# artik530_carrierboard.net
KiCad netlist of a schematic drawn in EAGLE
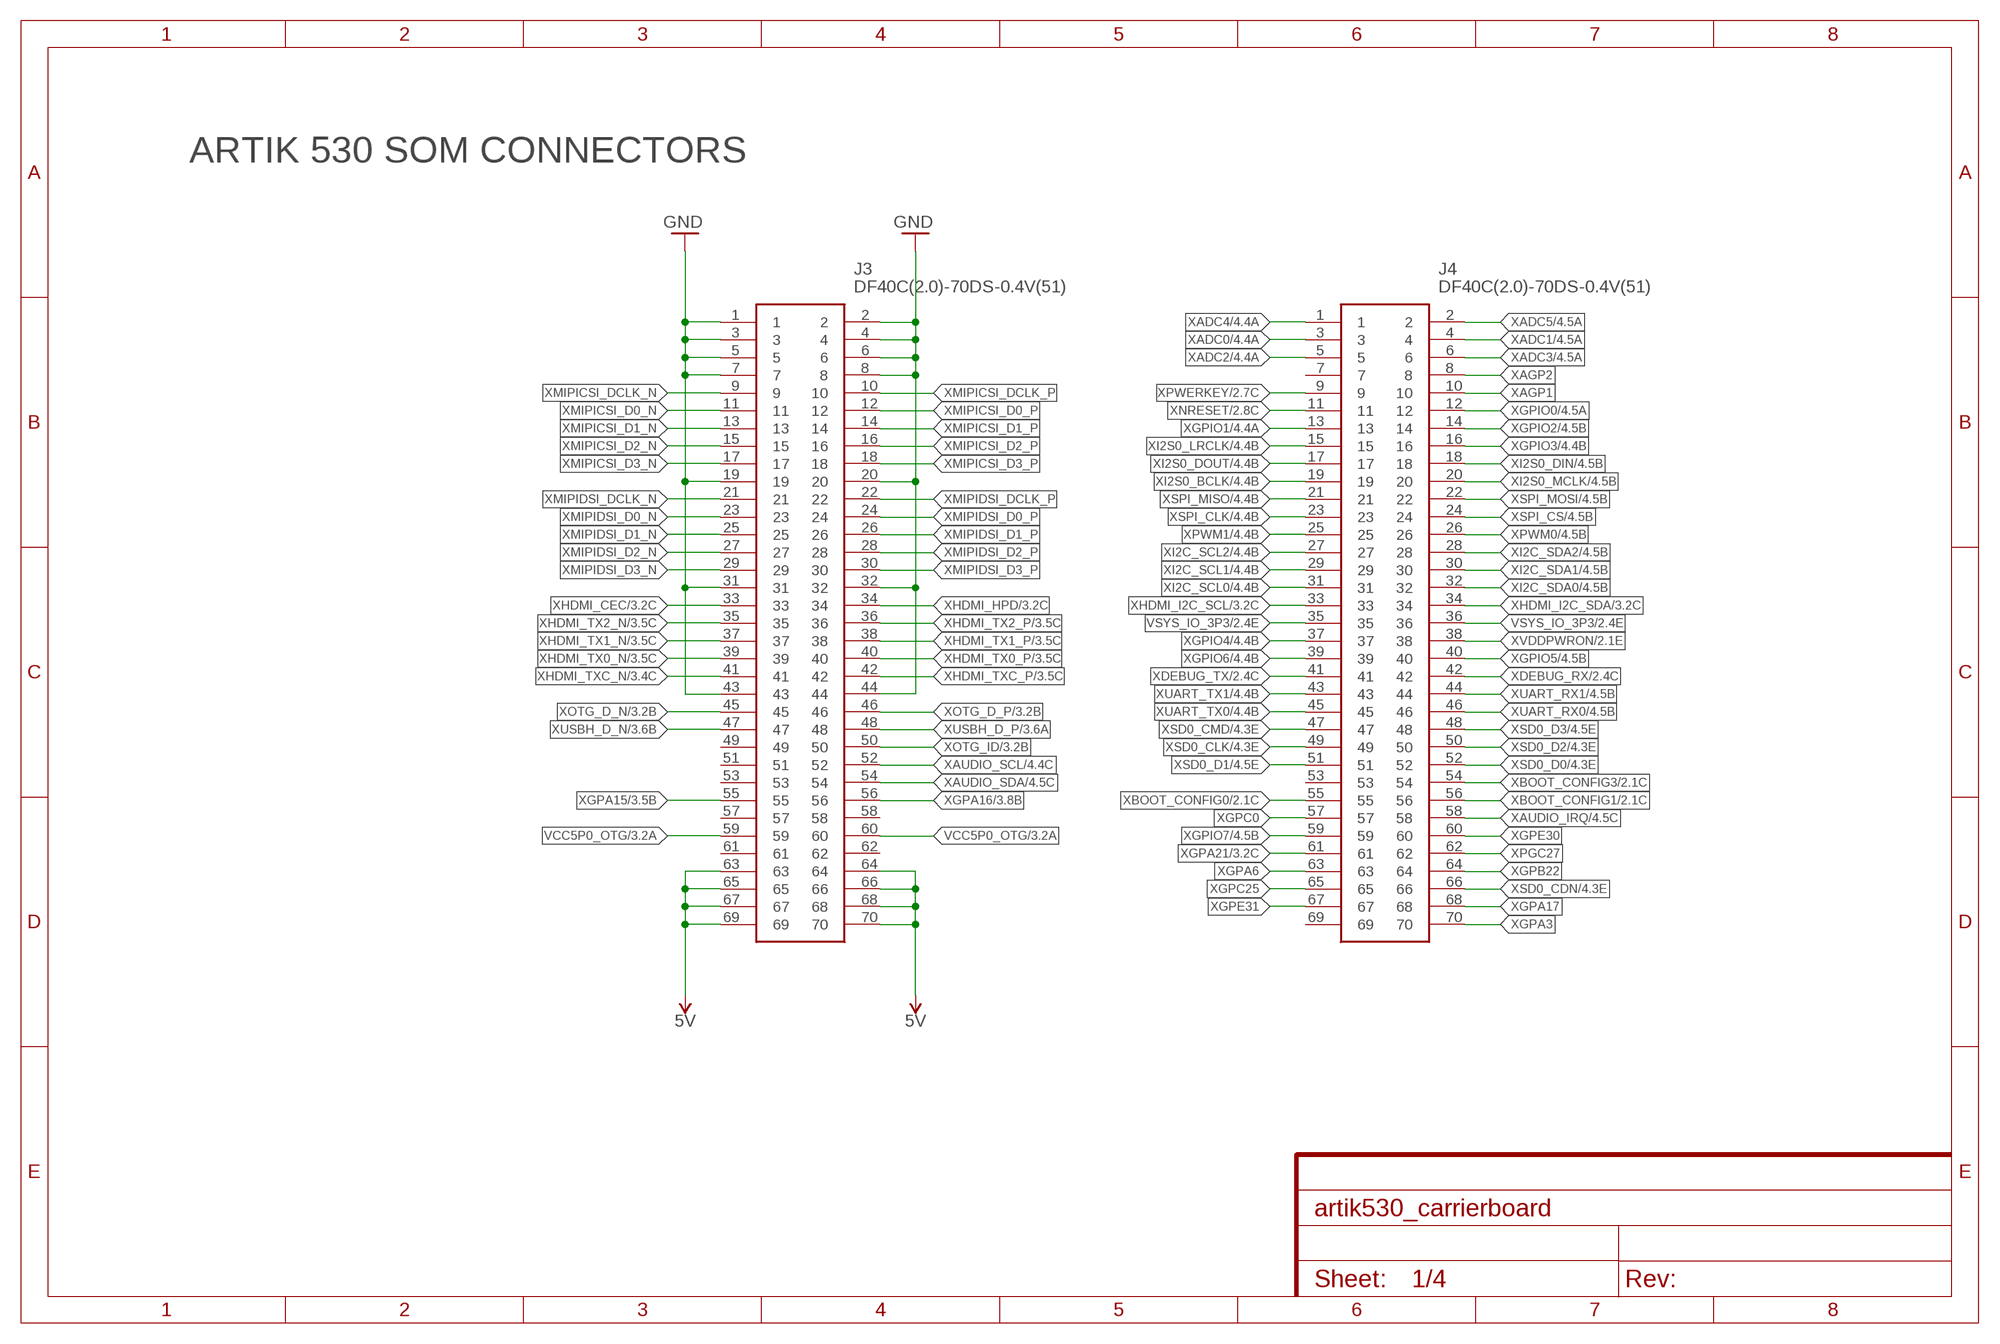
[diagram p0: schematic, sheet 1]
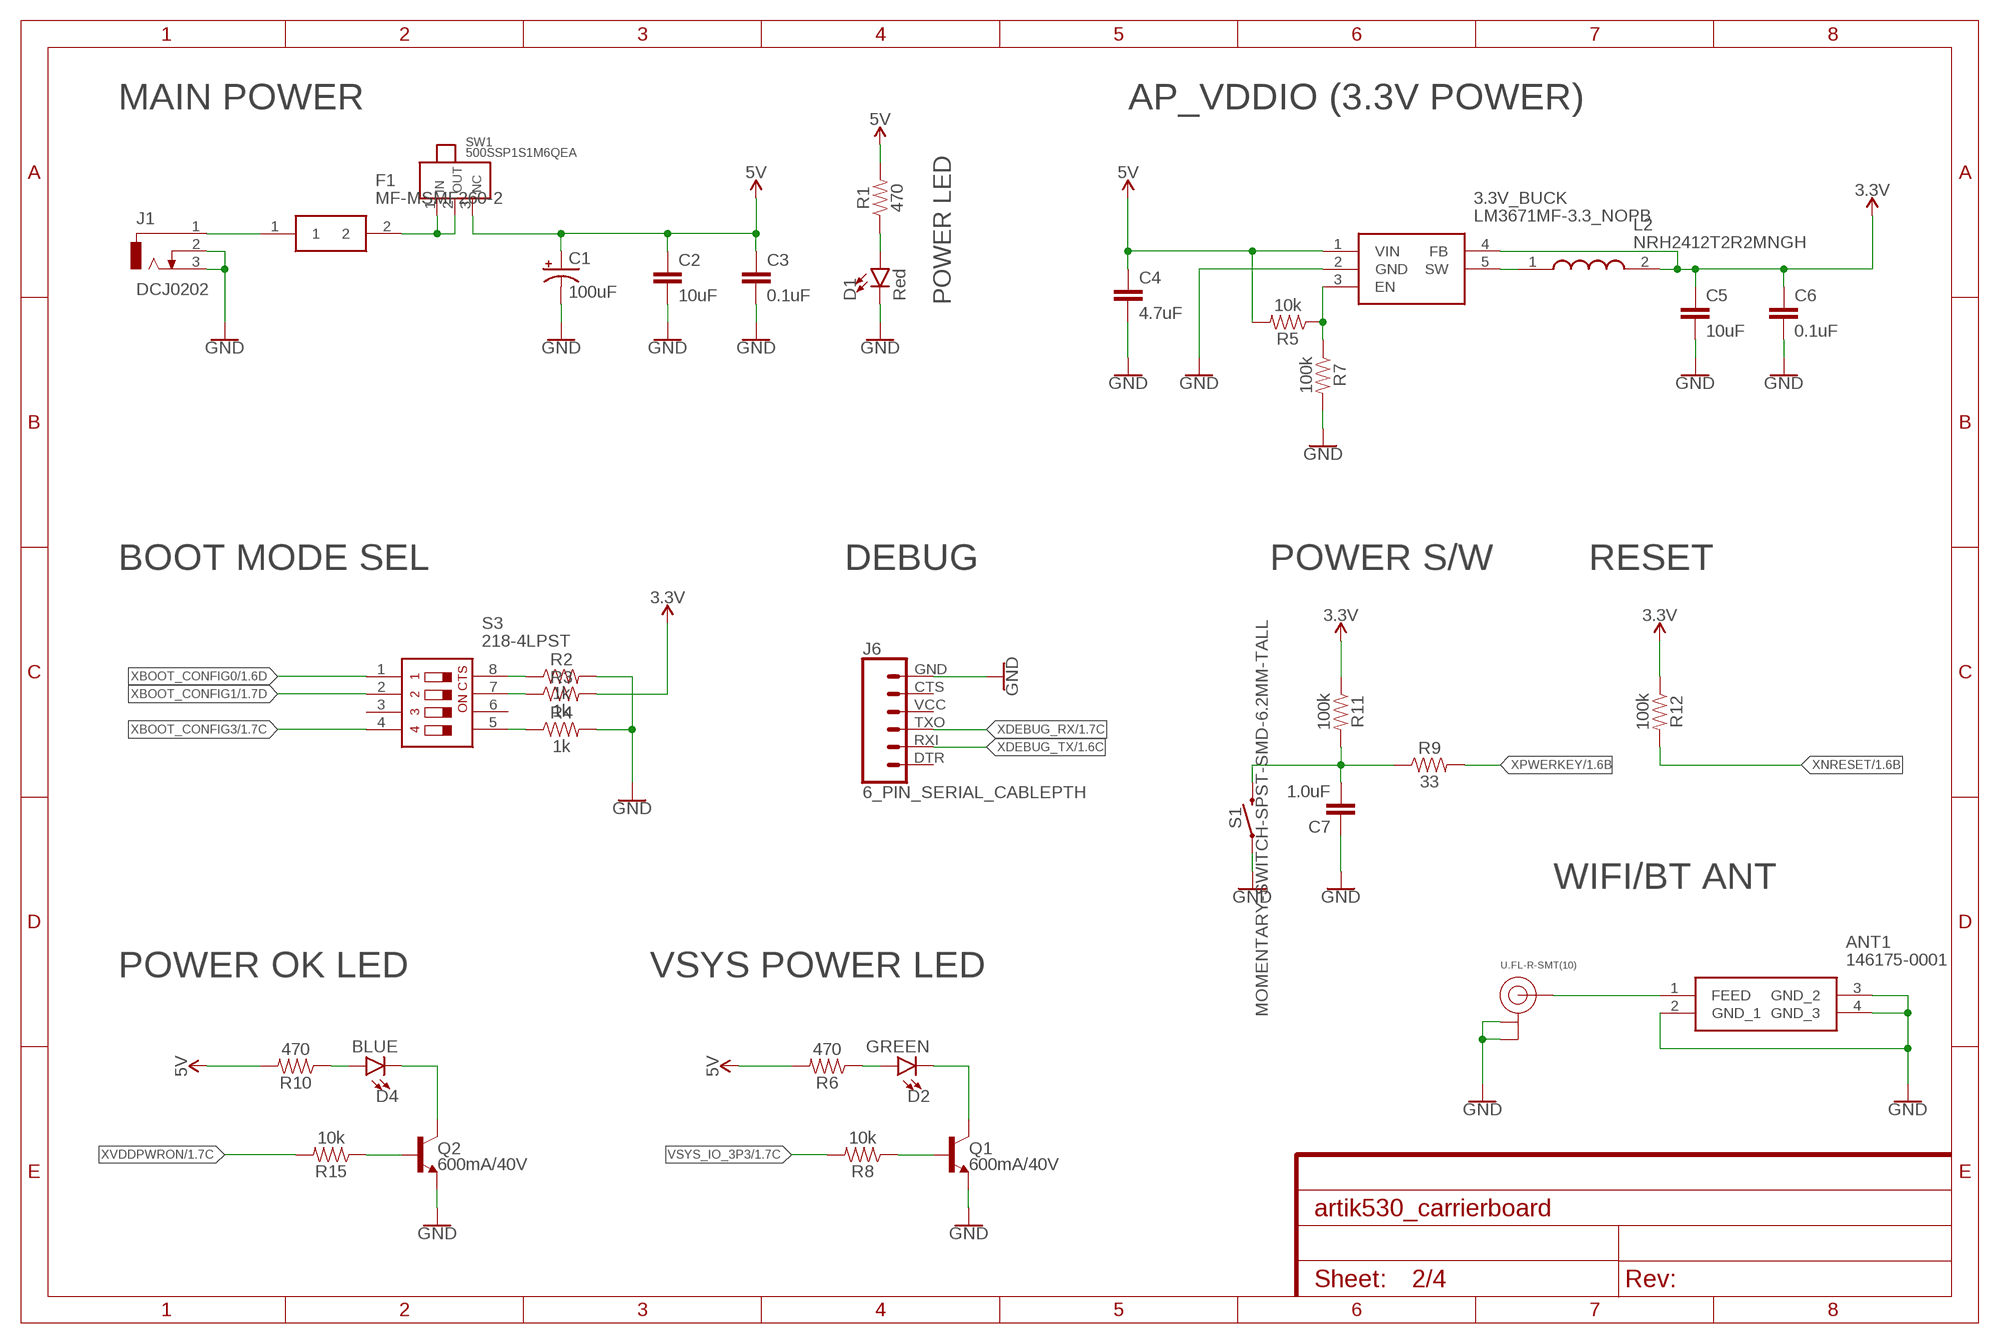
[diagram p1: schematic, sheet 2]
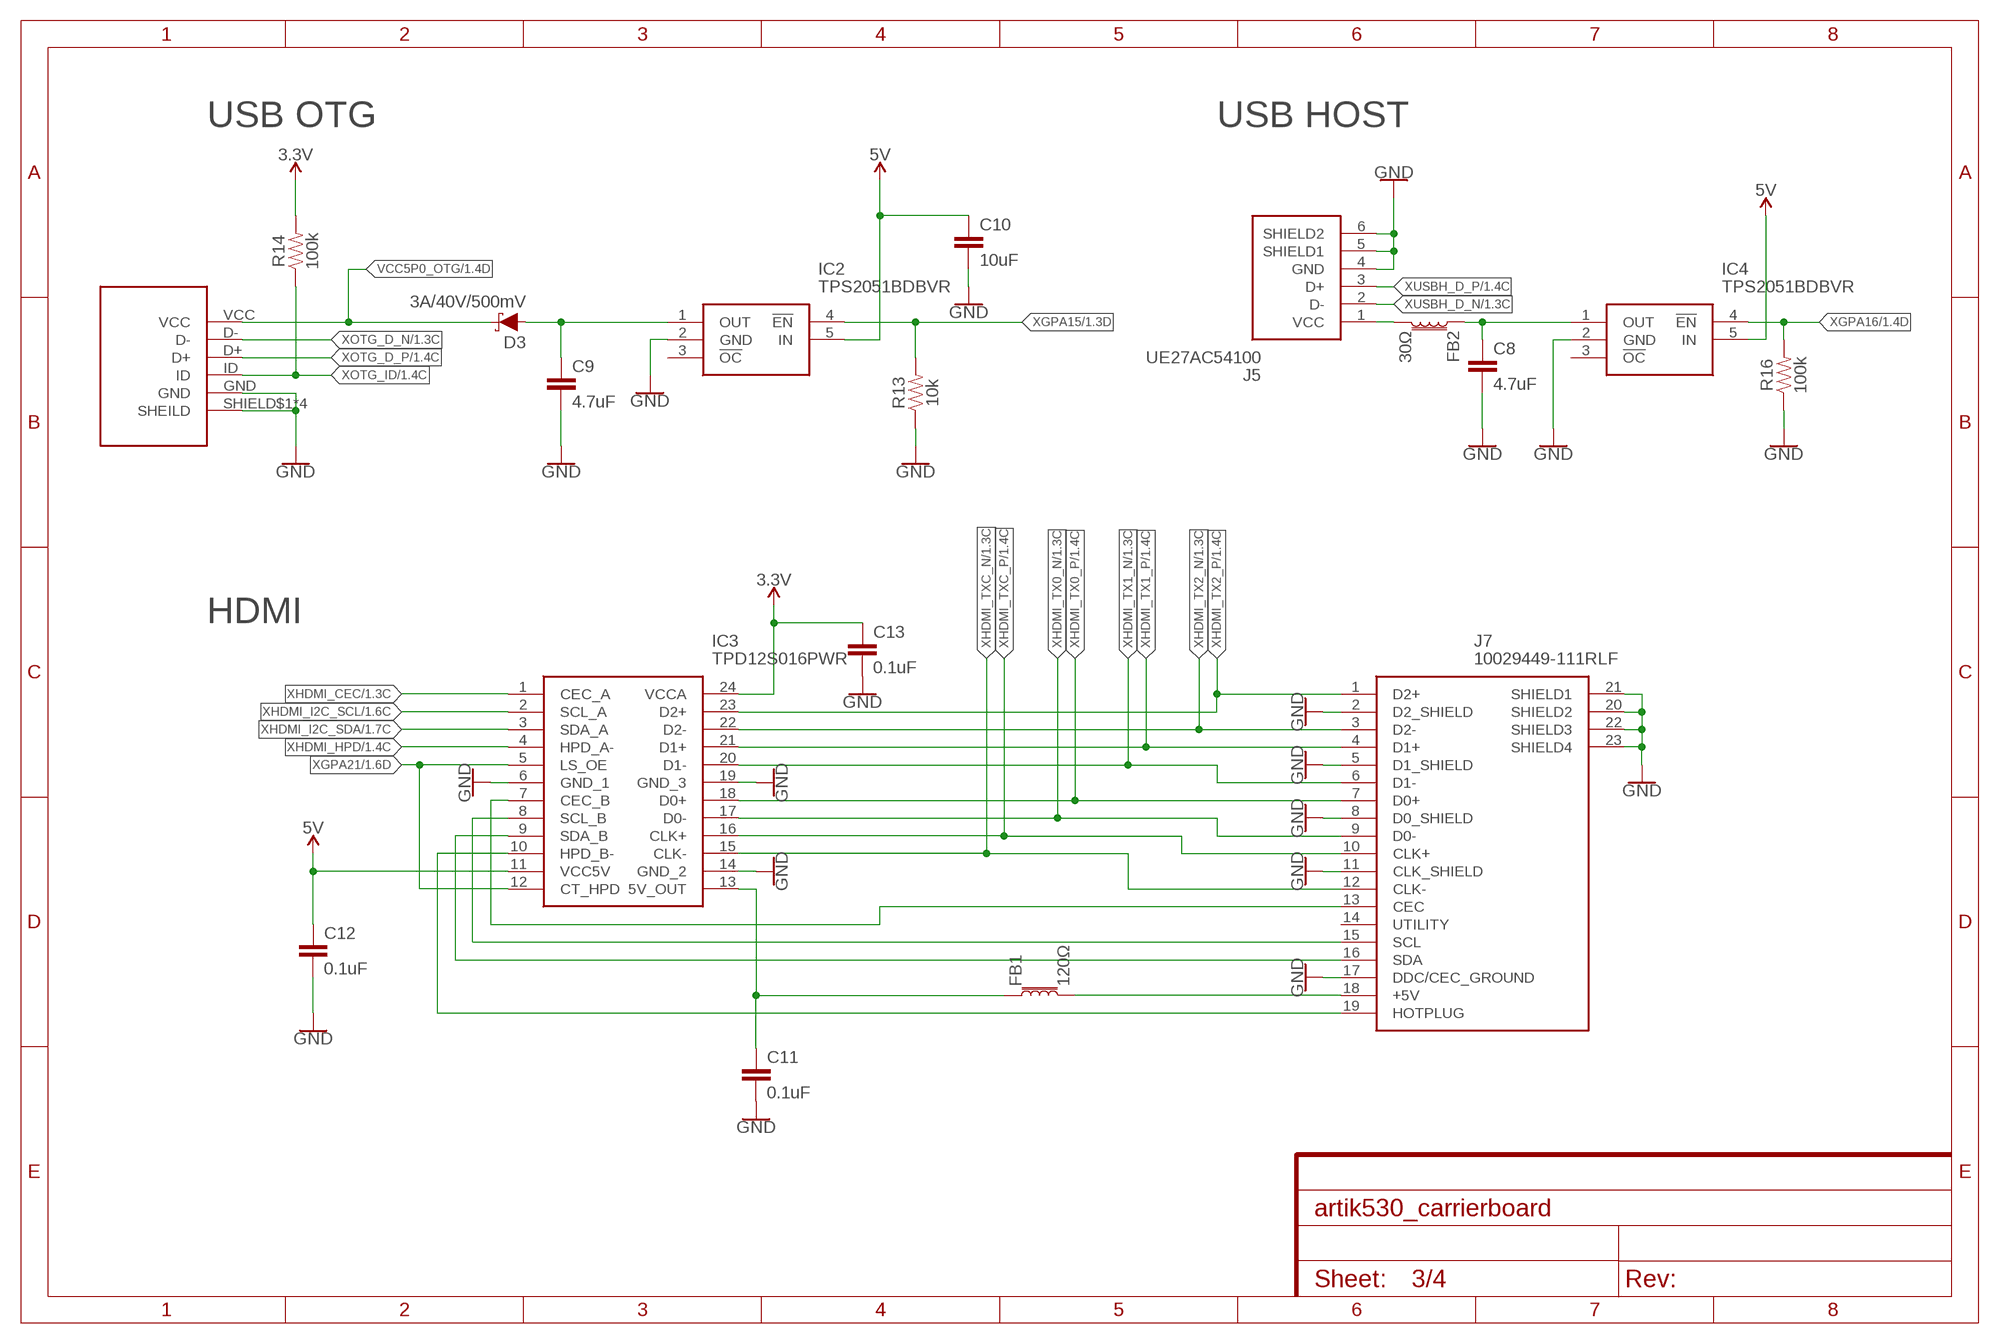
[diagram p2: schematic, sheet 3]
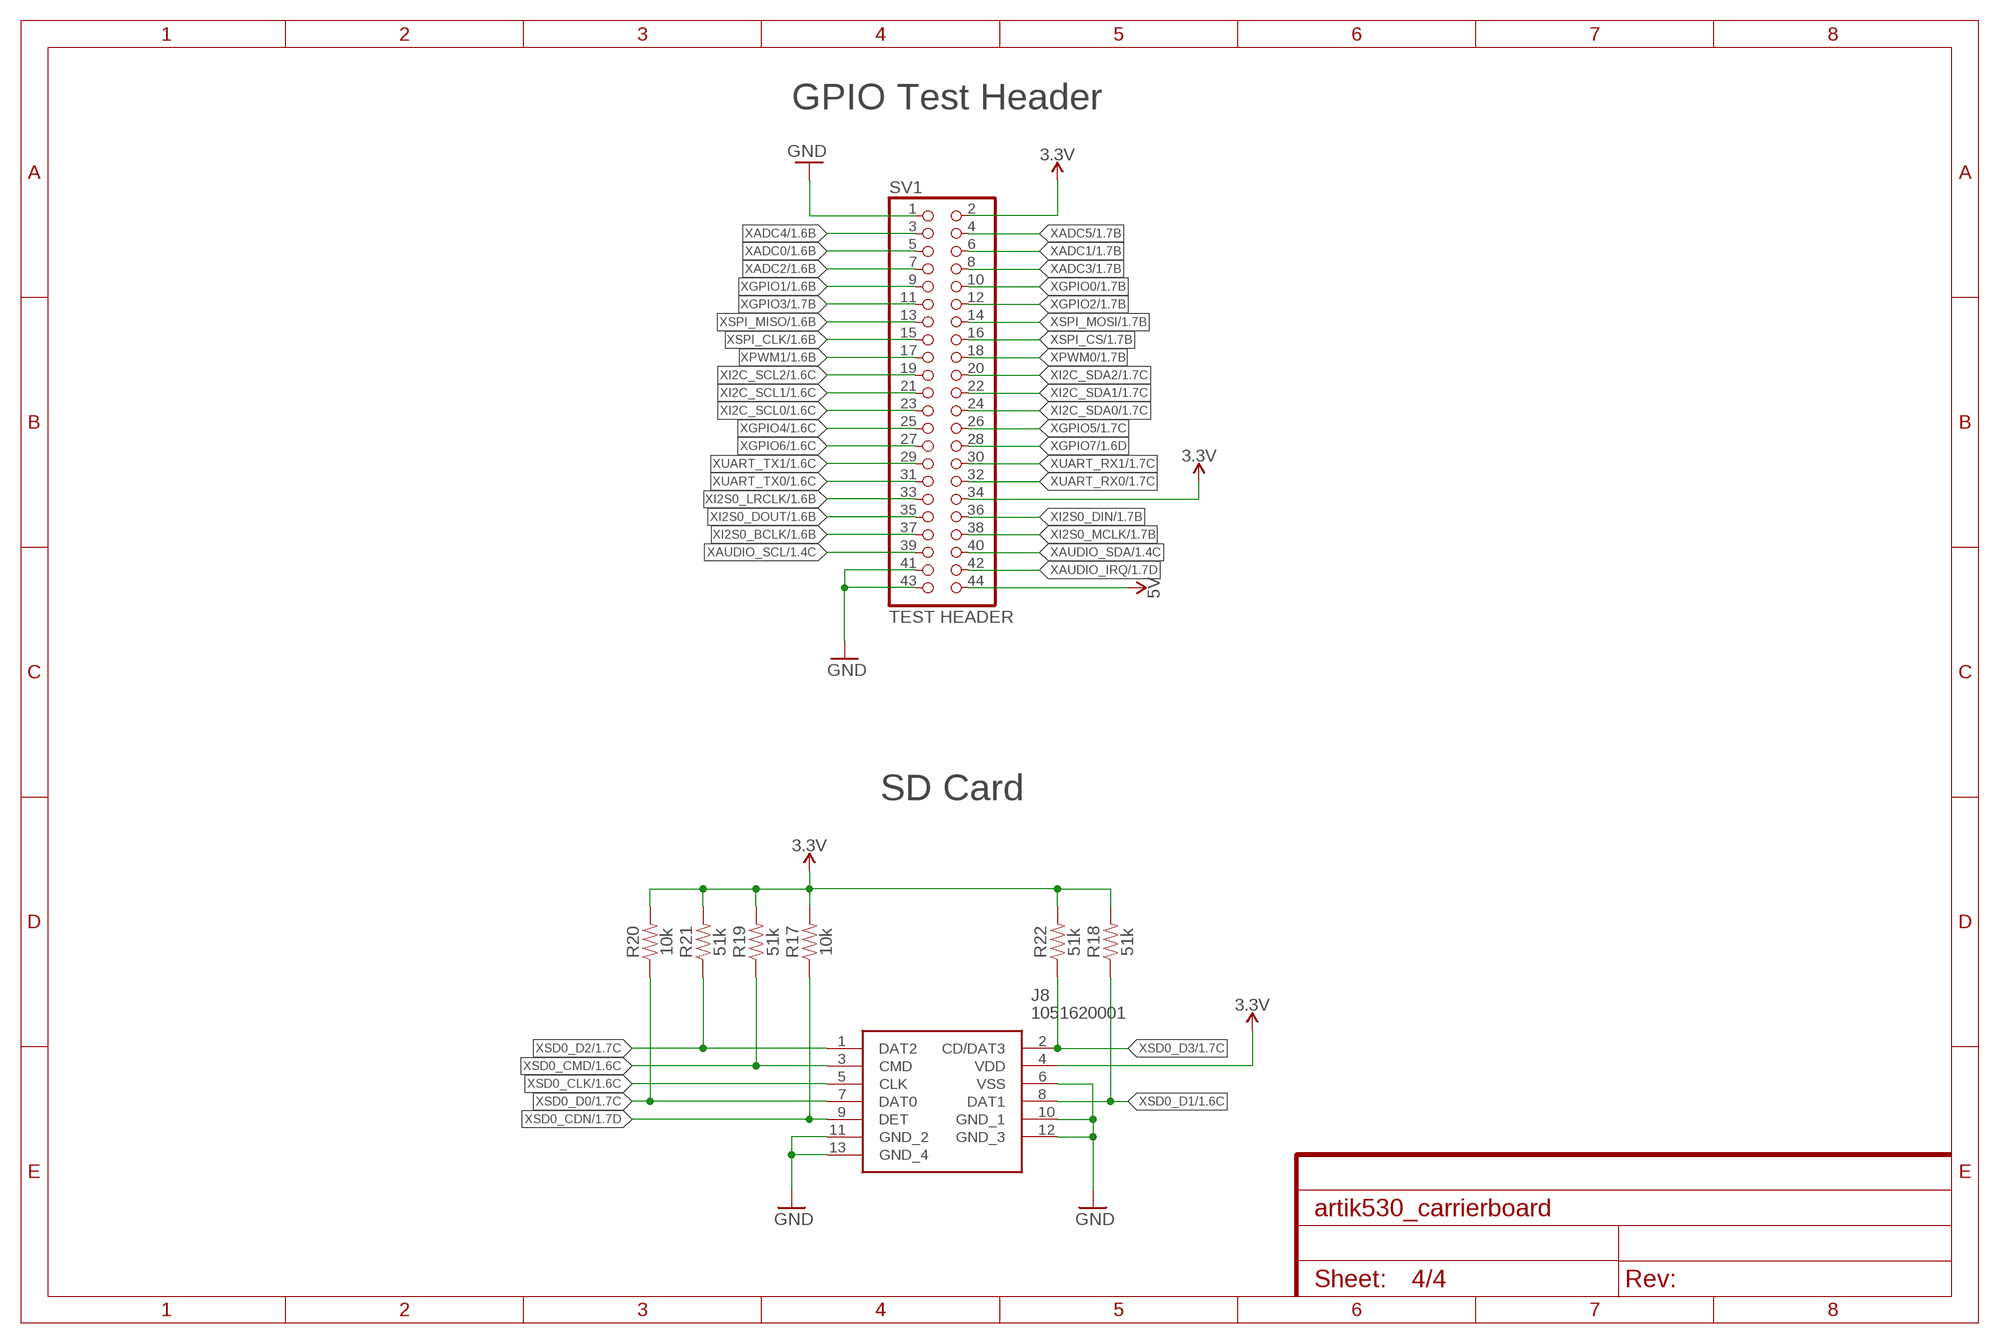
[diagram p3: schematic, sheet 4]

(export (version "E")
  (design (tool "Eeschema 10.0.6"))
  (components
    (comp (ref "C8")
      (value "4.7uF")
      (footprint "eagle-import:0603")
      (libsource (lib "eagle-import") (part "4.7UF-0603-6.3V-(10%)"))
    )
    (comp (ref "C9")
      (value "4.7uF")
      (footprint "eagle-import:0603")
      (libsource (lib "eagle-import") (part "4.7UF-0603-6.3V-(10%)"))
    )
    (comp (ref "C10")
      (value "10uF")
      (footprint "eagle-import:0603")
      (libsource (lib "eagle-import") (part "10UF-0603-6.3V-20%"))
    )
    (comp (ref "C11")
      (value "0.1uF")
      (footprint "eagle-import:0603")
      (libsource (lib "eagle-import") (part "0.1UF-0603-25V-(+80/-20%)"))
    )
    (comp (ref "C12")
      (value "0.1uF")
      (footprint "eagle-import:0603")
      (libsource (lib "eagle-import") (part "0.1UF-0603-25V-(+80/-20%)"))
    )
    (comp (ref "C13")
      (value "0.1uF")
      (footprint "eagle-import:0603")
      (libsource (lib "eagle-import") (part "0.1UF-0603-25V-(+80/-20%)"))
    )
    (comp (ref "D3")
      (value "3A/40V/500mV")
      (footprint "eagle-import:SMA-DIODE")
      (libsource (lib "eagle-import") (part "DIODE-SCHOTTKY-B340A"))
    )
    (comp (ref "FB1")
      (value "120Ω")
      (footprint "eagle-import:0603")
      (libsource (lib "eagle-import") (part "FERRITE_BEAD-0603"))
    )
    (comp (ref "FB2")
      (value "30Ω")
      (footprint "eagle-import:0603")
      (libsource (lib "eagle-import") (part "FERRITE_BEAD-0603"))
    )
    (comp (ref "IC2")
      (value "TPS2051BDBVR")
      (footprint "eagle-import:SOT95P280X145-5N")
      (libsource (lib "eagle-import") (part "TPS2051BDBVR"))
    )
    (comp (ref "IC3")
      (value "TPD12S016PWR")
      (footprint "eagle-import:SOP65P640X120-24N")
      (fields (field (name "RS_PART_NUMBER") "1627865"))
      (libsource (lib "eagle-import") (part "TPD12S016PWR"))
    )
    (comp (ref "IC4")
      (value "TPS2051BDBVR")
      (footprint "eagle-import:SOT95P280X145-5N")
      (libsource (lib "eagle-import") (part "TPS2051BDBVR"))
    )
    (comp (ref "J2")
      (value "10118193-0001LF")
      (footprint "eagle-import:10118193-0001LF")
      (libsource (lib "eagle-import") (part "10118193-0001LF"))
    )
    (comp (ref "J5")
      (value "UE27AC54100")
      (footprint "eagle-import:UE27AC54100")
      (libsource (lib "eagle-import") (part "UE27AC54100"))
    )
    (comp (ref "J7")
      (value "10029449-111RLF")
      (footprint "eagle-import:10029449-111RLF_1")
      (libsource (lib "eagle-import") (part "10029449-111RLF"))
    )
    (comp (ref "R13")
      (value "10k")
      (footprint "eagle-import:0603")
      (libsource (lib "eagle-import") (part "10KOHM-0603-1/10W-1%"))
    )
    (comp (ref "R14")
      (value "100k")
      (footprint "eagle-import:0603")
      (libsource (lib "eagle-import") (part "100KOHM-0603-1/10W-1%"))
    )
    (comp (ref "R16")
      (value "100k")
      (footprint "eagle-import:0603")
      (libsource (lib "eagle-import") (part "100KOHM-0603-1/10W-1%"))
    )
    (comp (ref "3.3V_BUCK")
      (value "LM3671MF-3.3_NOPB")
      (footprint "eagle-import:SOT95P284X122-5N")
      (fields
        (field (name "DIGIKEY_PART_NUMBER") "LM3671MF-3.3/NOPBTR-ND")
        (field (name "MANUFACTURER_PART_NUMBER") "LM3671MF-3.3/NOPB")
      )
      (libsource (lib "eagle-import") (part "LM3671MF-3.3_NOPB"))
    )
    (comp (ref "ANT1")
      (value "146175-0001")
      (footprint "eagle-import:146175-0001")
      (libsource (lib "eagle-import") (part "146175-0001"))
    )
    (comp (ref "C1")
      (value "100uF")
      (footprint "eagle-import:EIA7343")
      (libsource (lib "eagle-import") (part "100UF-POLAR-EIA7343-10V-10%(TANT)"))
    )
    (comp (ref "C2")
      (value "10uF")
      (footprint "eagle-import:0603")
      (libsource (lib "eagle-import") (part "10UF-0603-6.3V-20%"))
    )
    (comp (ref "C3")
      (value "0.1uF")
      (footprint "eagle-import:0603")
      (libsource (lib "eagle-import") (part "0.1UF-0603-25V-(+80/-20%)"))
    )
    (comp (ref "C4")
      (value "4.7uF")
      (footprint "eagle-import:0603")
      (libsource (lib "eagle-import") (part "4.7UF-0603-6.3V-(10%)"))
    )
    (comp (ref "C5")
      (value "10uF")
      (footprint "eagle-import:0603")
      (libsource (lib "eagle-import") (part "10UF-0603-6.3V-20%"))
    )
    (comp (ref "C6")
      (value "0.1uF")
      (footprint "eagle-import:0603")
      (libsource (lib "eagle-import") (part "0.1UF-0603-25V-(+80/-20%)"))
    )
    (comp (ref "C7")
      (value "1.0uF")
      (footprint "eagle-import:0603")
      (libsource (lib "eagle-import") (part "1.0UF-0603-16V-10%"))
    )
    (comp (ref "D1")
      (value "Red")
      (footprint "eagle-import:LED-0603")
      (libsource (lib "eagle-import") (part "LED-RED0603-SMART"))
    )
    (comp (ref "D2")
      (value "GREEN")
      (footprint "eagle-import:LED-0603")
      (libsource (lib "eagle-import") (part "LED-GREEN0603"))
    )
    (comp (ref "D4")
      (value "BLUE")
      (footprint "eagle-import:LED-0603")
      (libsource (lib "eagle-import") (part "LED-GREEN0603"))
    )
    (comp (ref "F1")
      (value "MF-MSMF260-2")
      (footprint "eagle-import:MF-MSMF260-2")
      (fields (field (name "RS_PART_NUMBER") "6478257P"))
      (libsource (lib "eagle-import") (part "MF-MSMF260-2"))
    )
    (comp (ref "J1")
      (value "DCJ0202")
      (footprint "eagle-import:DCJ0202")
      (libsource (lib "eagle-import") (part "DCJ0202"))
    )
    (comp (ref "J6")
      (value "6_PIN_SERIAL_CABLEPTH")
      (footprint "eagle-import:FTDI_BASIC")
      (libsource (lib "eagle-import") (part "6_PIN_SERIAL_CABLEPTH"))
    )
    (comp (ref "L2")
      (value "NRH2412T2R2MNGH")
      (footprint "eagle-import:NRH2412T2R2MNGH")
      (libsource (lib "eagle-import") (part "NRH2412T2R2MNGH"))
    )
    (comp (ref "Q1")
      (value "600mA/40V")
      (footprint "eagle-import:SOT23-3")
      (libsource (lib "eagle-import") (part "TRANS_NPN-MMBT2222AL"))
    )
    (comp (ref "Q2")
      (value "600mA/40V")
      (footprint "eagle-import:SOT23-3")
      (libsource (lib "eagle-import") (part "TRANS_NPN-MMBT2222AL"))
    )
    (comp (ref "R1")
      (value "470")
      (footprint "eagle-import:0603")
      (libsource (lib "eagle-import") (part "470OHM-0603-1/10W-1%"))
    )
    (comp (ref "R2")
      (value "1k")
      (footprint "eagle-import:0603")
      (libsource (lib "eagle-import") (part "1KOHM-0603-1/10W-1%"))
    )
    (comp (ref "R3")
      (value "1k")
      (footprint "eagle-import:0603")
      (libsource (lib "eagle-import") (part "1KOHM-0603-1/10W-1%"))
    )
    (comp (ref "R4")
      (value "1k")
      (footprint "eagle-import:0603")
      (libsource (lib "eagle-import") (part "1KOHM-0603-1/10W-1%"))
    )
    (comp (ref "R5")
      (value "10k")
      (footprint "eagle-import:0603")
      (libsource (lib "eagle-import") (part "10KOHM-0603-1/10W-1%"))
    )
    (comp (ref "R6")
      (value "470")
      (footprint "eagle-import:0603")
      (libsource (lib "eagle-import") (part "470OHM-0603-1/10W-1%"))
    )
    (comp (ref "R7")
      (value "100k")
      (footprint "eagle-import:0603")
      (libsource (lib "eagle-import") (part "100KOHM-0603-1/10W-1%"))
    )
    (comp (ref "R8")
      (value "10k")
      (footprint "eagle-import:0603")
      (libsource (lib "eagle-import") (part "10KOHM-0603-1/10W-1%"))
    )
    (comp (ref "R9")
      (value "33")
      (footprint "eagle-import:0603")
      (libsource (lib "eagle-import") (part "33OHM-0603-1/10W-1%"))
    )
    (comp (ref "R10")
      (value "470")
      (footprint "eagle-import:0603")
      (libsource (lib "eagle-import") (part "470OHM-0603-1/10W-1%"))
    )
    (comp (ref "R11")
      (value "100k")
      (footprint "eagle-import:0603")
      (libsource (lib "eagle-import") (part "100KOHM-0603-1/10W-1%"))
    )
    (comp (ref "R12")
      (value "100k")
      (footprint "eagle-import:0603")
      (libsource (lib "eagle-import") (part "100KOHM-0603-1/10W-1%"))
    )
    (comp (ref "R15")
      (value "10k")
      (footprint "eagle-import:0603")
      (libsource (lib "eagle-import") (part "10KOHM-0603-1/10W-1%"))
    )
    (comp (ref "S1")
      (value "MOMENTARY-SWITCH-SPST-SMD-6.2MM-TALL")
      (footprint "eagle-import:TACTILE_SWITCH_SMD_6.2MM_TALL")
      (libsource (lib "eagle-import") (part "MOMENTARY-SWITCH-SPST-SMD-6.2MM-TALL"))
    )
    (comp (ref "S3")
      (value "218-4LPST")
      (footprint "eagle-import:SOIC127P844X265-8N")
      (libsource (lib "eagle-import") (part "218-4LPST"))
    )
    (comp (ref "SW1")
      (value "500SSP1S1M6QEA")
      (footprint "eagle-import:500SSP1S1M6QEA")
      (libsource (lib "eagle-import") (part "500SSP1S1M6QEA"))
    )
    (comp (ref "U$3")
      (value "U.FL-R-SMT(10)")
      (footprint "eagle-import:U.FL-R-SMT(10)")
      (libsource (lib "eagle-import") (part "U.FL-R-SMT(10)"))
    )
    (comp (ref "J3")
      (value "DF40C(2.0)-70DS-0.4V(51)")
      (footprint "eagle-import:DF40C(2.0)-70DS-0.4V(51)")
      (libsource (lib "eagle-import") (part "DF40C(2.0)-70DS-0.4V(51)"))
    )
    (comp (ref "J4")
      (value "DF40C(2.0)-70DS-0.4V(51)")
      (footprint "eagle-import:DF40C(2.0)-70DS-0.4V(51)")
      (libsource (lib "eagle-import") (part "DF40C(2.0)-70DS-0.4V(51)"))
    )
    (comp (ref "J8")
      (value "1051620001")
      (footprint "eagle-import:1051620001")
      (libsource (lib "eagle-import") (part "1051620001"))
    )
    (comp (ref "R17")
      (value "10k")
      (footprint "eagle-import:0603")
      (libsource (lib "eagle-import") (part "10KOHM-0603-1/10W-1%"))
    )
    (comp (ref "R18")
      (value "51k")
      (footprint "eagle-import:0603")
      (libsource (lib "eagle-import") (part "10KOHM-0603-1/10W-1%"))
    )
    (comp (ref "R19")
      (value "51k")
      (footprint "eagle-import:0603")
      (libsource (lib "eagle-import") (part "10KOHM-0603-1/10W-1%"))
    )
    (comp (ref "R20")
      (value "10k")
      (footprint "eagle-import:0603")
      (libsource (lib "eagle-import") (part "10KOHM-0603-1/10W-1%"))
    )
    (comp (ref "R21")
      (value "51k")
      (footprint "eagle-import:0603")
      (libsource (lib "eagle-import") (part "10KOHM-0603-1/10W-1%"))
    )
    (comp (ref "R22")
      (value "51k")
      (footprint "eagle-import:0603")
      (libsource (lib "eagle-import") (part "10KOHM-0603-1/10W-1%"))
    )
    (comp (ref "SV1")
      (value "TEST HEADER")
      (footprint "eagle-import:2X22")
      (libsource (lib "eagle-import") (part "PINHD-2X22"))
    )
  )
  (nets
    (net (code "1") (name "3.3V") (class "Default")
      (node (ref "3.3V_BUCK") (pin "4") (pinfunction "FB_4") (pintype "bidirectional"))
      (node (ref "C13") (pin "1") (pinfunction "1_1") (pintype "passive"))
      (node (ref "C5") (pin "1") (pinfunction "1_1") (pintype "passive"))
      (node (ref "C6") (pin "1") (pinfunction "1_1") (pintype "passive"))
      (node (ref "IC3") (pin "24") (pinfunction "VCCA_24") (pintype "bidirectional"))
      (node (ref "J8") (pin "4") (pinfunction "VDD_4") (pintype "bidirectional"))
      (node (ref "L2") (pin "2") (pinfunction "2_2") (pintype "bidirectional"))
      (node (ref "R11") (pin "1") (pinfunction "1_1") (pintype "passive"))
      (node (ref "R12") (pin "1") (pinfunction "1_1") (pintype "passive"))
      (node (ref "R14") (pin "2") (pinfunction "2_2") (pintype "passive"))
      (node (ref "R17") (pin "2") (pinfunction "2_2") (pintype "passive"))
      (node (ref "R18") (pin "2") (pinfunction "2_2") (pintype "passive"))
      (node (ref "R19") (pin "2") (pinfunction "2_2") (pintype "passive"))
      (node (ref "R20") (pin "2") (pinfunction "2_2") (pintype "passive"))
      (node (ref "R21") (pin "2") (pinfunction "2_2") (pintype "passive"))
      (node (ref "R22") (pin "2") (pinfunction "2_2") (pintype "passive"))
      (node (ref "R3") (pin "2") (pinfunction "2_2") (pintype "passive"))
      (node (ref "SV1") (pin "2") (pinfunction "2_2") (pintype "passive"))
      (node (ref "SV1") (pin "34") (pinfunction "34_34") (pintype "passive"))
    )
    (net (code "2") (name "5V") (class "Default")
      (node (ref "3.3V_BUCK") (pin "1") (pinfunction "VIN_1") (pintype "bidirectional"))
      (node (ref "C1") (pin "A") (pinfunction "+_A") (pintype "passive"))
      (node (ref "C10") (pin "1") (pinfunction "1_1") (pintype "passive"))
      (node (ref "C12") (pin "1") (pinfunction "1_1") (pintype "passive"))
      (node (ref "C2") (pin "1") (pinfunction "1_1") (pintype "passive"))
      (node (ref "C3") (pin "1") (pinfunction "1_1") (pintype "passive"))
      (node (ref "C4") (pin "1") (pinfunction "1_1") (pintype "passive"))
      (node (ref "IC2") (pin "5") (pinfunction "IN_5") (pintype "input"))
      (node (ref "IC3") (pin "11") (pinfunction "VCC5V_11") (pintype "bidirectional"))
      (node (ref "IC4") (pin "5") (pinfunction "IN_5") (pintype "input"))
      (node (ref "J3") (pin "63") (pinfunction "63_63") (pintype "bidirectional"))
      (node (ref "J3") (pin "64") (pinfunction "64_64") (pintype "bidirectional"))
      (node (ref "J3") (pin "65") (pinfunction "65_65") (pintype "bidirectional"))
      (node (ref "J3") (pin "66") (pinfunction "66_66") (pintype "bidirectional"))
      (node (ref "J3") (pin "67") (pinfunction "67_67") (pintype "bidirectional"))
      (node (ref "J3") (pin "68") (pinfunction "68_68") (pintype "bidirectional"))
      (node (ref "J3") (pin "69") (pinfunction "69_69") (pintype "bidirectional"))
      (node (ref "J3") (pin "70") (pinfunction "70_70") (pintype "bidirectional"))
      (node (ref "R1") (pin "2") (pinfunction "2_2") (pintype "passive"))
      (node (ref "R10") (pin "2") (pinfunction "2_2") (pintype "passive"))
      (node (ref "R5") (pin "2") (pinfunction "2_2") (pintype "passive"))
      (node (ref "R6") (pin "2") (pinfunction "2_2") (pintype "passive"))
      (node (ref "SV1") (pin "44") (pinfunction "44_44") (pintype "passive"))
      (node (ref "SW1") (pin "3") (pinfunction "NC_3") (pintype "bidirectional"))
    )
    (net (code "3") (name "GND") (class "Default")
      (node (ref "3.3V_BUCK") (pin "2") (pinfunction "GND_2") (pintype "bidirectional"))
      (node (ref "ANT1") (pin "2") (pinfunction "GND_1_2") (pintype "bidirectional"))
      (node (ref "ANT1") (pin "3") (pinfunction "GND_2_3") (pintype "bidirectional"))
      (node (ref "ANT1") (pin "4") (pinfunction "GND_3_4") (pintype "bidirectional"))
      (node (ref "C1") (pin "C") (pinfunction "-_C") (pintype "passive"))
      (node (ref "C10") (pin "2") (pinfunction "2_2") (pintype "passive"))
      (node (ref "C11") (pin "2") (pinfunction "2_2") (pintype "passive"))
      (node (ref "C12") (pin "2") (pinfunction "2_2") (pintype "passive"))
      (node (ref "C13") (pin "2") (pinfunction "2_2") (pintype "passive"))
      (node (ref "C2") (pin "2") (pinfunction "2_2") (pintype "passive"))
      (node (ref "C3") (pin "2") (pinfunction "2_2") (pintype "passive"))
      (node (ref "C4") (pin "2") (pinfunction "2_2") (pintype "passive"))
      (node (ref "C5") (pin "2") (pinfunction "2_2") (pintype "passive"))
      (node (ref "C6") (pin "2") (pinfunction "2_2") (pintype "passive"))
      (node (ref "C7") (pin "1") (pinfunction "1_1") (pintype "passive"))
      (node (ref "C8") (pin "2") (pinfunction "2_2") (pintype "passive"))
      (node (ref "C9") (pin "2") (pinfunction "2_2") (pintype "passive"))
      (node (ref "D1") (pin "C") (pinfunction "C_C") (pintype "passive"))
      (node (ref "IC2") (pin "2") (pinfunction "GND_2") (pintype "power_in"))
      (node (ref "IC3") (pin "14") (pinfunction "GND_2_14") (pintype "bidirectional"))
      (node (ref "IC3") (pin "19") (pinfunction "GND_3_19") (pintype "bidirectional"))
      (node (ref "IC3") (pin "6") (pinfunction "GND_1_6") (pintype "bidirectional"))
      (node (ref "IC4") (pin "2") (pinfunction "GND_2") (pintype "power_in"))
      (node (ref "J1") (pin "2") (pinfunction "2_2") (pintype "passive"))
      (node (ref "J1") (pin "3") (pinfunction "3_3") (pintype "passive"))
      (node (ref "J2") (pin "GND") (pinfunction "GND_GND") (pintype "bidirectional"))
      (node (ref "J2") (pin "SHIELD$1") (pinfunction "SHEILD_SHIELD$1") (pintype "bidirectional"))
      (node (ref "J2") (pin "SHIELD$2") (pinfunction "SHEILD_SHIELD$2") (pintype "bidirectional"))
      (node (ref "J2") (pin "SHIELD$3") (pinfunction "SHEILD_SHIELD$3") (pintype "bidirectional"))
      (node (ref "J2") (pin "SHIELD$4") (pinfunction "SHEILD_SHIELD$4") (pintype "bidirectional"))
      (node (ref "J3") (pin "1") (pinfunction "1_1") (pintype "bidirectional"))
      (node (ref "J3") (pin "19") (pinfunction "19_19") (pintype "bidirectional"))
      (node (ref "J3") (pin "2") (pinfunction "2_2") (pintype "bidirectional"))
      (node (ref "J3") (pin "20") (pinfunction "20_20") (pintype "bidirectional"))
      (node (ref "J3") (pin "3") (pinfunction "3_3") (pintype "bidirectional"))
      (node (ref "J3") (pin "31") (pinfunction "31_31") (pintype "bidirectional"))
      (node (ref "J3") (pin "32") (pinfunction "32_32") (pintype "bidirectional"))
      (node (ref "J3") (pin "4") (pinfunction "4_4") (pintype "bidirectional"))
      (node (ref "J3") (pin "43") (pinfunction "43_43") (pintype "bidirectional"))
      (node (ref "J3") (pin "44") (pinfunction "44_44") (pintype "bidirectional"))
      (node (ref "J3") (pin "5") (pinfunction "5_5") (pintype "bidirectional"))
      (node (ref "J3") (pin "6") (pinfunction "6_6") (pintype "bidirectional"))
      (node (ref "J3") (pin "7") (pinfunction "7_7") (pintype "bidirectional"))
      (node (ref "J3") (pin "8") (pinfunction "8_8") (pintype "bidirectional"))
      (node (ref "J5") (pin "4") (pinfunction "GND_4") (pintype "bidirectional"))
      (node (ref "J5") (pin "5") (pinfunction "SHIELD1_5") (pintype "bidirectional"))
      (node (ref "J5") (pin "6") (pinfunction "SHIELD2_6") (pintype "bidirectional"))
      (node (ref "J6") (pin "GND") (pinfunction "6_GND") (pintype "passive"))
      (node (ref "J7") (pin "11") (pinfunction "CLK_SHIELD_11") (pintype "bidirectional"))
      (node (ref "J7") (pin "17") (pinfunction "DDC/CEC_GROUND_17") (pintype "bidirectional"))
      (node (ref "J7") (pin "2") (pinfunction "D2_SHIELD_2") (pintype "bidirectional"))
      (node (ref "J7") (pin "20") (pinfunction "SHIELD2_20") (pintype "bidirectional"))
      (node (ref "J7") (pin "21") (pinfunction "SHIELD1_21") (pintype "bidirectional"))
      (node (ref "J7") (pin "22") (pinfunction "SHIELD3_22") (pintype "bidirectional"))
      (node (ref "J7") (pin "23") (pinfunction "SHIELD4_23") (pintype "bidirectional"))
      (node (ref "J7") (pin "5") (pinfunction "D1_SHIELD_5") (pintype "bidirectional"))
      (node (ref "J7") (pin "8") (pinfunction "D0_SHIELD_8") (pintype "bidirectional"))
      (node (ref "J8") (pin "10") (pinfunction "GND_1_10") (pintype "bidirectional"))
      (node (ref "J8") (pin "11") (pinfunction "GND_2_11") (pintype "bidirectional"))
      (node (ref "J8") (pin "12") (pinfunction "GND_3_12") (pintype "bidirectional"))
      (node (ref "J8") (pin "13") (pinfunction "GND_4_13") (pintype "bidirectional"))
      (node (ref "J8") (pin "6") (pinfunction "VSS_6") (pintype "bidirectional"))
      (node (ref "Q1") (pin "2") (pinfunction "E_2") (pintype "passive"))
      (node (ref "Q2") (pin "2") (pinfunction "E_2") (pintype "passive"))
      (node (ref "R13") (pin "1") (pinfunction "1_1") (pintype "passive"))
      (node (ref "R16") (pin "1") (pinfunction "1_1") (pintype "passive"))
      (node (ref "R2") (pin "2") (pinfunction "2_2") (pintype "passive"))
      (node (ref "R4") (pin "2") (pinfunction "2_2") (pintype "passive"))
      (node (ref "R7") (pin "2") (pinfunction "2_2") (pintype "passive"))
      (node (ref "S1") (pin "A2") (pinfunction "1_A2") (pintype "passive"))
      (node (ref "SV1") (pin "1") (pinfunction "1_1") (pintype "passive"))
      (node (ref "SV1") (pin "41") (pinfunction "41_41") (pintype "passive"))
      (node (ref "SV1") (pin "43") (pinfunction "43_43") (pintype "passive"))
      (node (ref "U$3") (pin "1") (pinfunction "GND1_1") (pintype "bidirectional"))
      (node (ref "U$3") (pin "2") (pinfunction "GND2_2") (pintype "bidirectional"))
    )
    (net (code "4") (name "Net-(3.3V_BUCK-EN)") (class "Default")
      (node (ref "3.3V_BUCK") (pin "3") (pinfunction "EN_3") (pintype "bidirectional"))
      (node (ref "R5") (pin "1") (pinfunction "1_1") (pintype "passive"))
      (node (ref "R7") (pin "1") (pinfunction "1_1") (pintype "passive"))
    )
    (net (code "5") (name "Net-(3.3V_BUCK-SW)") (class "Default")
      (node (ref "3.3V_BUCK") (pin "5") (pinfunction "SW_5") (pintype "bidirectional"))
      (node (ref "L2") (pin "1") (pinfunction "1_1") (pintype "bidirectional"))
    )
    (net (code "6") (name "Net-(ANT1-FEED)") (class "Default")
      (node (ref "ANT1") (pin "1") (pinfunction "FEED_1") (pintype "bidirectional"))
      (node (ref "U$3") (pin "3") (pinfunction "SIG_3") (pintype "bidirectional"))
    )
    (net (code "7") (name "Net-(D1-PadA)") (class "Default")
      (node (ref "D1") (pin "A") (pinfunction "A_A") (pintype "passive"))
      (node (ref "R1") (pin "1") (pinfunction "1_1") (pintype "passive"))
    )
    (net (code "8") (name "Net-(D2-PadA)") (class "Default")
      (node (ref "D2") (pin "A") (pinfunction "A_A") (pintype "passive"))
      (node (ref "R6") (pin "1") (pinfunction "1_1") (pintype "passive"))
    )
    (net (code "9") (name "Net-(D4-PadA)") (class "Default")
      (node (ref "D4") (pin "A") (pinfunction "A_A") (pintype "passive"))
      (node (ref "R10") (pin "1") (pinfunction "1_1") (pintype "passive"))
    )
    (net (code "10") (name "Net-(F1-Pad1)") (class "Default")
      (node (ref "F1") (pin "1") (pinfunction "1_1") (pintype "bidirectional"))
      (node (ref "J1") (pin "1") (pinfunction "1_1") (pintype "passive"))
    )
    (net (code "11") (name "Net-(IC2-OUT)") (class "Default")
      (node (ref "C9") (pin "1") (pinfunction "1_1") (pintype "passive"))
      (node (ref "D3") (pin "A") (pinfunction "A_A") (pintype "passive"))
      (node (ref "IC2") (pin "1") (pinfunction "OUT_1") (pintype "output"))
    )
    (net (code "12") (name "Net-(IC3-5V_OUT)") (class "Default")
      (node (ref "C11") (pin "1") (pinfunction "1_1") (pintype "passive"))
      (node (ref "FB1") (pin "1") (pinfunction "1_1") (pintype "passive"))
      (node (ref "IC3") (pin "13") (pinfunction "5V_OUT_13") (pintype "output"))
    )
    (net (code "13") (name "Net-(IC3-CEC_B)") (class "Default")
      (node (ref "IC3") (pin "7") (pinfunction "CEC_B_7") (pintype "bidirectional"))
      (node (ref "J7") (pin "13") (pinfunction "CEC_13") (pintype "bidirectional"))
    )
    (net (code "14") (name "Net-(IC3-HPD_B-)") (class "Default")
      (node (ref "IC3") (pin "10") (pinfunction "HPD_B-_10") (pintype "bidirectional"))
      (node (ref "J7") (pin "19") (pinfunction "HOTPLUG_19") (pintype "bidirectional"))
    )
    (net (code "15") (name "Net-(IC3-SCL_B)") (class "Default")
      (node (ref "IC3") (pin "8") (pinfunction "SCL_B_8") (pintype "bidirectional"))
      (node (ref "J7") (pin "15") (pinfunction "SCL_15") (pintype "bidirectional"))
    )
    (net (code "16") (name "Net-(IC3-SDA_B)") (class "Default")
      (node (ref "IC3") (pin "9") (pinfunction "SDA_B_9") (pintype "bidirectional"))
      (node (ref "J7") (pin "16") (pinfunction "SDA_16") (pintype "bidirectional"))
    )
    (net (code "17") (name "Net-(IC4-OUT)") (class "Default")
      (node (ref "C8") (pin "1") (pinfunction "1_1") (pintype "passive"))
      (node (ref "FB2") (pin "1") (pinfunction "1_1") (pintype "passive"))
      (node (ref "IC4") (pin "1") (pinfunction "OUT_1") (pintype "output"))
    )
    (net (code "18") (name "Net-(J5-VCC)") (class "Default")
      (node (ref "FB2") (pin "2") (pinfunction "2_2") (pintype "passive"))
      (node (ref "J5") (pin "1") (pinfunction "VCC_1") (pintype "bidirectional"))
    )
    (net (code "19") (name "Net-(J7-+5V)") (class "Default")
      (node (ref "FB1") (pin "2") (pinfunction "2_2") (pintype "passive"))
      (node (ref "J7") (pin "18") (pinfunction "+5V_18") (pintype "bidirectional"))
    )
    (net (code "20") (name "Net-(Q1-B)") (class "Default")
      (node (ref "Q1") (pin "1") (pinfunction "B_1") (pintype "passive"))
      (node (ref "R8") (pin "1") (pinfunction "1_1") (pintype "passive"))
    )
    (net (code "21") (name "Net-(Q1-C)") (class "Default")
      (node (ref "D2") (pin "C") (pinfunction "C_C") (pintype "passive"))
      (node (ref "Q1") (pin "3") (pinfunction "C_3") (pintype "passive"))
    )
    (net (code "22") (name "Net-(Q2-B)") (class "Default")
      (node (ref "Q2") (pin "1") (pinfunction "B_1") (pintype "passive"))
      (node (ref "R15") (pin "1") (pinfunction "1_1") (pintype "passive"))
    )
    (net (code "23") (name "Net-(Q2-C)") (class "Default")
      (node (ref "D4") (pin "C") (pinfunction "C_C") (pintype "passive"))
      (node (ref "Q2") (pin "3") (pinfunction "C_3") (pintype "passive"))
    )
    (net (code "24") (name "Net-(R2-Pad1)") (class "Default")
      (node (ref "R2") (pin "1") (pinfunction "1_1") (pintype "passive"))
      (node (ref "S3") (pin "8") (pinfunction "8_8") (pintype "bidirectional"))
    )
    (net (code "25") (name "Net-(R3-Pad1)") (class "Default")
      (node (ref "R3") (pin "1") (pinfunction "1_1") (pintype "passive"))
      (node (ref "S3") (pin "7") (pinfunction "7_7") (pintype "bidirectional"))
    )
    (net (code "26") (name "Net-(R4-Pad1)") (class "Default")
      (node (ref "R4") (pin "1") (pinfunction "1_1") (pintype "passive"))
      (node (ref "S3") (pin "5") (pinfunction "5_5") (pintype "bidirectional"))
    )
    (net (code "27") (name "Net-(S1-2)") (class "Default")
      (node (ref "C7") (pin "2") (pinfunction "2_2") (pintype "passive"))
      (node (ref "R11") (pin "2") (pinfunction "2_2") (pintype "passive"))
      (node (ref "R9") (pin "1") (pinfunction "1_1") (pintype "passive"))
      (node (ref "S1") (pin "B2") (pinfunction "2_B2") (pintype "passive"))
    )
    (net (code "28") (name "Net-(SW1-IN)") (class "Default")
      (node (ref "F1") (pin "2") (pinfunction "2_2") (pintype "bidirectional"))
      (node (ref "SW1") (pin "1") (pinfunction "IN_1") (pintype "bidirectional"))
      (node (ref "SW1") (pin "2") (pinfunction "OUT_2") (pintype "bidirectional"))
    )
    (net (code "29") (name "VCC5P0_OTG") (class "Default")
      (node (ref "D3") (pin "C") (pinfunction "C_C") (pintype "passive"))
      (node (ref "J2") (pin "VCC") (pinfunction "VCC_VCC") (pintype "bidirectional"))
      (node (ref "J3") (pin "59") (pinfunction "59_59") (pintype "bidirectional"))
      (node (ref "J3") (pin "60") (pinfunction "60_60") (pintype "bidirectional"))
    )
    (net (code "30") (name "VSYS_IO_3P3") (class "Default")
      (node (ref "J4") (pin "35") (pinfunction "35_35") (pintype "bidirectional"))
      (node (ref "J4") (pin "36") (pinfunction "36_36") (pintype "bidirectional"))
      (node (ref "R8") (pin "2") (pinfunction "2_2") (pintype "passive"))
    )
    (net (code "31") (name "XADC0") (class "Default")
      (node (ref "J4") (pin "3") (pinfunction "3_3") (pintype "bidirectional"))
      (node (ref "SV1") (pin "5") (pinfunction "5_5") (pintype "passive"))
    )
    (net (code "32") (name "XADC1") (class "Default")
      (node (ref "J4") (pin "4") (pinfunction "4_4") (pintype "bidirectional"))
      (node (ref "SV1") (pin "6") (pinfunction "6_6") (pintype "passive"))
    )
    (net (code "33") (name "XADC2") (class "Default")
      (node (ref "J4") (pin "5") (pinfunction "5_5") (pintype "bidirectional"))
      (node (ref "SV1") (pin "7") (pinfunction "7_7") (pintype "passive"))
    )
    (net (code "34") (name "XADC3") (class "Default")
      (node (ref "J4") (pin "6") (pinfunction "6_6") (pintype "bidirectional"))
      (node (ref "SV1") (pin "8") (pinfunction "8_8") (pintype "passive"))
    )
    (net (code "35") (name "XADC4") (class "Default")
      (node (ref "J4") (pin "1") (pinfunction "1_1") (pintype "bidirectional"))
      (node (ref "SV1") (pin "3") (pinfunction "3_3") (pintype "passive"))
    )
    (net (code "36") (name "XADC5") (class "Default")
      (node (ref "J4") (pin "2") (pinfunction "2_2") (pintype "bidirectional"))
      (node (ref "SV1") (pin "4") (pinfunction "4_4") (pintype "passive"))
    )
    (net (code "37") (name "XAGP1") (class "Default")
      (node (ref "J4") (pin "10") (pinfunction "10_10") (pintype "bidirectional"))
    )
    (net (code "38") (name "XAGP2") (class "Default")
      (node (ref "J4") (pin "8") (pinfunction "8_8") (pintype "bidirectional"))
    )
    (net (code "39") (name "XAUDIO_IRQ") (class "Default")
      (node (ref "J4") (pin "58") (pinfunction "58_58") (pintype "bidirectional"))
      (node (ref "SV1") (pin "42") (pinfunction "42_42") (pintype "passive"))
    )
    (net (code "40") (name "XAUDIO_SCL") (class "Default")
      (node (ref "J3") (pin "52") (pinfunction "52_52") (pintype "bidirectional"))
      (node (ref "SV1") (pin "39") (pinfunction "39_39") (pintype "passive"))
    )
    (net (code "41") (name "XAUDIO_SDA") (class "Default")
      (node (ref "J3") (pin "54") (pinfunction "54_54") (pintype "bidirectional"))
      (node (ref "SV1") (pin "40") (pinfunction "40_40") (pintype "passive"))
    )
    (net (code "42") (name "XBOOT_CONFIG0") (class "Default")
      (node (ref "J4") (pin "55") (pinfunction "55_55") (pintype "bidirectional"))
      (node (ref "S3") (pin "1") (pinfunction "1_1") (pintype "bidirectional"))
    )
    (net (code "43") (name "XBOOT_CONFIG1") (class "Default")
      (node (ref "J4") (pin "56") (pinfunction "56_56") (pintype "bidirectional"))
      (node (ref "S3") (pin "2") (pinfunction "2_2") (pintype "bidirectional"))
    )
    (net (code "44") (name "XBOOT_CONFIG3") (class "Default")
      (node (ref "J4") (pin "54") (pinfunction "54_54") (pintype "bidirectional"))
      (node (ref "S3") (pin "4") (pinfunction "4_4") (pintype "bidirectional"))
    )
    (net (code "45") (name "XDEBUG_RX") (class "Default")
      (node (ref "J4") (pin "42") (pinfunction "42_42") (pintype "bidirectional"))
      (node (ref "J6") (pin "TXO") (pinfunction "3_TXO") (pintype "passive"))
    )
    (net (code "46") (name "XDEBUG_TX") (class "Default")
      (node (ref "J4") (pin "41") (pinfunction "41_41") (pintype "bidirectional"))
      (node (ref "J6") (pin "RXI") (pinfunction "2_RXI") (pintype "passive"))
    )
    (net (code "47") (name "XGPA3") (class "Default")
      (node (ref "J4") (pin "70") (pinfunction "70_70") (pintype "bidirectional"))
    )
    (net (code "48") (name "XGPA6") (class "Default")
      (node (ref "J4") (pin "63") (pinfunction "63_63") (pintype "bidirectional"))
    )
    (net (code "49") (name "XGPA15") (class "Default")
      (node (ref "IC2") (pin "4") (pinfunction "~{EN}_4") (pintype "bidirectional"))
      (node (ref "J3") (pin "55") (pinfunction "55_55") (pintype "bidirectional"))
      (node (ref "R13") (pin "2") (pinfunction "2_2") (pintype "passive"))
    )
    (net (code "50") (name "XGPA16") (class "Default")
      (node (ref "IC4") (pin "4") (pinfunction "~{EN}_4") (pintype "bidirectional"))
      (node (ref "J3") (pin "56") (pinfunction "56_56") (pintype "bidirectional"))
      (node (ref "R16") (pin "2") (pinfunction "2_2") (pintype "passive"))
    )
    (net (code "51") (name "XGPA17") (class "Default")
      (node (ref "J4") (pin "68") (pinfunction "68_68") (pintype "bidirectional"))
    )
    (net (code "52") (name "XGPA21") (class "Default")
      (node (ref "IC3") (pin "12") (pinfunction "CT_HPD_12") (pintype "bidirectional"))
      (node (ref "IC3") (pin "5") (pinfunction "LS_OE_5") (pintype "bidirectional"))
      (node (ref "J4") (pin "61") (pinfunction "61_61") (pintype "bidirectional"))
    )
    (net (code "53") (name "XGPB22") (class "Default")
      (node (ref "J4") (pin "64") (pinfunction "64_64") (pintype "bidirectional"))
    )
    (net (code "54") (name "XGPC0") (class "Default")
      (node (ref "J4") (pin "57") (pinfunction "57_57") (pintype "bidirectional"))
    )
    (net (code "55") (name "XGPC25") (class "Default")
      (node (ref "J4") (pin "65") (pinfunction "65_65") (pintype "bidirectional"))
    )
    (net (code "56") (name "XGPE30") (class "Default")
      (node (ref "J4") (pin "60") (pinfunction "60_60") (pintype "bidirectional"))
    )
    (net (code "57") (name "XGPE31") (class "Default")
      (node (ref "J4") (pin "67") (pinfunction "67_67") (pintype "bidirectional"))
    )
    (net (code "58") (name "XGPIO0") (class "Default")
      (node (ref "J4") (pin "12") (pinfunction "12_12") (pintype "bidirectional"))
      (node (ref "SV1") (pin "10") (pinfunction "10_10") (pintype "passive"))
    )
    (net (code "59") (name "XGPIO1") (class "Default")
      (node (ref "J4") (pin "13") (pinfunction "13_13") (pintype "bidirectional"))
      (node (ref "SV1") (pin "9") (pinfunction "9_9") (pintype "passive"))
    )
    (net (code "60") (name "XGPIO2") (class "Default")
      (node (ref "J4") (pin "14") (pinfunction "14_14") (pintype "bidirectional"))
      (node (ref "SV1") (pin "12") (pinfunction "12_12") (pintype "passive"))
    )
    (net (code "61") (name "XGPIO3") (class "Default")
      (node (ref "J4") (pin "16") (pinfunction "16_16") (pintype "bidirectional"))
      (node (ref "SV1") (pin "11") (pinfunction "11_11") (pintype "passive"))
    )
    (net (code "62") (name "XGPIO4") (class "Default")
      (node (ref "J4") (pin "37") (pinfunction "37_37") (pintype "bidirectional"))
      (node (ref "SV1") (pin "25") (pinfunction "25_25") (pintype "passive"))
    )
    (net (code "63") (name "XGPIO5") (class "Default")
      (node (ref "J4") (pin "40") (pinfunction "40_40") (pintype "bidirectional"))
      (node (ref "SV1") (pin "26") (pinfunction "26_26") (pintype "passive"))
    )
    (net (code "64") (name "XGPIO6") (class "Default")
      (node (ref "J4") (pin "39") (pinfunction "39_39") (pintype "bidirectional"))
      (node (ref "SV1") (pin "27") (pinfunction "27_27") (pintype "passive"))
    )
    (net (code "65") (name "XGPIO7") (class "Default")
      (node (ref "J4") (pin "59") (pinfunction "59_59") (pintype "bidirectional"))
      (node (ref "SV1") (pin "28") (pinfunction "28_28") (pintype "passive"))
    )
    (net (code "66") (name "XHDMI_CEC") (class "Default")
      (node (ref "IC3") (pin "1") (pinfunction "CEC_A_1") (pintype "bidirectional"))
      (node (ref "J3") (pin "33") (pinfunction "33_33") (pintype "bidirectional"))
    )
    (net (code "67") (name "XHDMI_HPD") (class "Default")
      (node (ref "IC3") (pin "4") (pinfunction "HPD_A-_4") (pintype "bidirectional"))
      (node (ref "J3") (pin "34") (pinfunction "34_34") (pintype "bidirectional"))
    )
    (net (code "68") (name "XHDMI_I2C_SCL") (class "Default")
      (node (ref "IC3") (pin "2") (pinfunction "SCL_A_2") (pintype "bidirectional"))
      (node (ref "J4") (pin "33") (pinfunction "33_33") (pintype "bidirectional"))
    )
    (net (code "69") (name "XHDMI_I2C_SDA") (class "Default")
      (node (ref "IC3") (pin "3") (pinfunction "SDA_A_3") (pintype "bidirectional"))
      (node (ref "J4") (pin "34") (pinfunction "34_34") (pintype "bidirectional"))
    )
    (net (code "70") (name "XHDMI_TX0_N") (class "Default")
      (node (ref "IC3") (pin "17") (pinfunction "D0-_17") (pintype "bidirectional"))
      (node (ref "J3") (pin "39") (pinfunction "39_39") (pintype "bidirectional"))
      (node (ref "J7") (pin "9") (pinfunction "D0-_9") (pintype "bidirectional"))
    )
    (net (code "71") (name "XHDMI_TX0_P") (class "Default")
      (node (ref "IC3") (pin "18") (pinfunction "D0+_18") (pintype "bidirectional"))
      (node (ref "J3") (pin "40") (pinfunction "40_40") (pintype "bidirectional"))
      (node (ref "J7") (pin "7") (pinfunction "D0+_7") (pintype "bidirectional"))
    )
    (net (code "72") (name "XHDMI_TX1_N") (class "Default")
      (node (ref "IC3") (pin "20") (pinfunction "D1-_20") (pintype "bidirectional"))
      (node (ref "J3") (pin "37") (pinfunction "37_37") (pintype "bidirectional"))
      (node (ref "J7") (pin "6") (pinfunction "D1-_6") (pintype "bidirectional"))
    )
    (net (code "73") (name "XHDMI_TX1_P") (class "Default")
      (node (ref "IC3") (pin "21") (pinfunction "D1+_21") (pintype "bidirectional"))
      (node (ref "J3") (pin "38") (pinfunction "38_38") (pintype "bidirectional"))
      (node (ref "J7") (pin "4") (pinfunction "D1+_4") (pintype "bidirectional"))
    )
    (net (code "74") (name "XHDMI_TX2_N") (class "Default")
      (node (ref "IC3") (pin "22") (pinfunction "D2-_22") (pintype "bidirectional"))
      (node (ref "J3") (pin "35") (pinfunction "35_35") (pintype "bidirectional"))
      (node (ref "J7") (pin "3") (pinfunction "D2-_3") (pintype "bidirectional"))
    )
    (net (code "75") (name "XHDMI_TX2_P") (class "Default")
      (node (ref "IC3") (pin "23") (pinfunction "D2+_23") (pintype "bidirectional"))
      (node (ref "J3") (pin "36") (pinfunction "36_36") (pintype "bidirectional"))
      (node (ref "J7") (pin "1") (pinfunction "D2+_1") (pintype "bidirectional"))
    )
    (net (code "76") (name "XHDMI_TXC_N") (class "Default")
      (node (ref "IC3") (pin "15") (pinfunction "CLK-_15") (pintype "input"))
      (node (ref "J3") (pin "41") (pinfunction "41_41") (pintype "bidirectional"))
      (node (ref "J7") (pin "12") (pinfunction "CLK-_12") (pintype "bidirectional"))
    )
    (net (code "77") (name "XHDMI_TXC_P") (class "Default")
      (node (ref "IC3") (pin "16") (pinfunction "CLK+_16") (pintype "input"))
      (node (ref "J3") (pin "42") (pinfunction "42_42") (pintype "bidirectional"))
      (node (ref "J7") (pin "10") (pinfunction "CLK+_10") (pintype "bidirectional"))
    )
    (net (code "78") (name "XI2C_SCL0") (class "Default")
      (node (ref "J4") (pin "31") (pinfunction "31_31") (pintype "bidirectional"))
      (node (ref "SV1") (pin "23") (pinfunction "23_23") (pintype "passive"))
    )
    (net (code "79") (name "XI2C_SCL1") (class "Default")
      (node (ref "J4") (pin "29") (pinfunction "29_29") (pintype "bidirectional"))
      (node (ref "SV1") (pin "21") (pinfunction "21_21") (pintype "passive"))
    )
    (net (code "80") (name "XI2C_SCL2") (class "Default")
      (node (ref "J4") (pin "27") (pinfunction "27_27") (pintype "bidirectional"))
      (node (ref "SV1") (pin "19") (pinfunction "19_19") (pintype "passive"))
    )
    (net (code "81") (name "XI2C_SDA0") (class "Default")
      (node (ref "J4") (pin "32") (pinfunction "32_32") (pintype "bidirectional"))
      (node (ref "SV1") (pin "24") (pinfunction "24_24") (pintype "passive"))
    )
    (net (code "82") (name "XI2C_SDA1") (class "Default")
      (node (ref "J4") (pin "30") (pinfunction "30_30") (pintype "bidirectional"))
      (node (ref "SV1") (pin "22") (pinfunction "22_22") (pintype "passive"))
    )
    (net (code "83") (name "XI2C_SDA2") (class "Default")
      (node (ref "J4") (pin "28") (pinfunction "28_28") (pintype "bidirectional"))
      (node (ref "SV1") (pin "20") (pinfunction "20_20") (pintype "passive"))
    )
    (net (code "84") (name "XI2S0_BCLK") (class "Default")
      (node (ref "J4") (pin "19") (pinfunction "19_19") (pintype "bidirectional"))
      (node (ref "SV1") (pin "37") (pinfunction "37_37") (pintype "passive"))
    )
    (net (code "85") (name "XI2S0_DIN") (class "Default")
      (node (ref "J4") (pin "18") (pinfunction "18_18") (pintype "bidirectional"))
      (node (ref "SV1") (pin "36") (pinfunction "36_36") (pintype "passive"))
    )
    (net (code "86") (name "XI2S0_DOUT") (class "Default")
      (node (ref "J4") (pin "17") (pinfunction "17_17") (pintype "bidirectional"))
      (node (ref "SV1") (pin "35") (pinfunction "35_35") (pintype "passive"))
    )
    (net (code "87") (name "XI2S0_LRCLK") (class "Default")
      (node (ref "J4") (pin "15") (pinfunction "15_15") (pintype "bidirectional"))
      (node (ref "SV1") (pin "33") (pinfunction "33_33") (pintype "passive"))
    )
    (net (code "88") (name "XI2S0_MCLK") (class "Default")
      (node (ref "J4") (pin "20") (pinfunction "20_20") (pintype "bidirectional"))
      (node (ref "SV1") (pin "38") (pinfunction "38_38") (pintype "passive"))
    )
    (net (code "89") (name "XMIPICSI_D0_N") (class "Default")
      (node (ref "J3") (pin "11") (pinfunction "11_11") (pintype "bidirectional"))
    )
    (net (code "90") (name "XMIPICSI_D0_P") (class "Default")
      (node (ref "J3") (pin "12") (pinfunction "12_12") (pintype "bidirectional"))
    )
    (net (code "91") (name "XMIPICSI_D1_N") (class "Default")
      (node (ref "J3") (pin "13") (pinfunction "13_13") (pintype "bidirectional"))
    )
    (net (code "92") (name "XMIPICSI_D1_P") (class "Default")
      (node (ref "J3") (pin "14") (pinfunction "14_14") (pintype "bidirectional"))
    )
    (net (code "93") (name "XMIPICSI_D2_N") (class "Default")
      (node (ref "J3") (pin "15") (pinfunction "15_15") (pintype "bidirectional"))
    )
    (net (code "94") (name "XMIPICSI_D2_P") (class "Default")
      (node (ref "J3") (pin "16") (pinfunction "16_16") (pintype "bidirectional"))
    )
    (net (code "95") (name "XMIPICSI_D3_N") (class "Default")
      (node (ref "J3") (pin "17") (pinfunction "17_17") (pintype "bidirectional"))
    )
    (net (code "96") (name "XMIPICSI_D3_P") (class "Default")
      (node (ref "J3") (pin "18") (pinfunction "18_18") (pintype "bidirectional"))
    )
    (net (code "97") (name "XMIPICSI_DCLK_N") (class "Default")
      (node (ref "J3") (pin "9") (pinfunction "9_9") (pintype "bidirectional"))
    )
    (net (code "98") (name "XMIPICSI_DCLK_P") (class "Default")
      (node (ref "J3") (pin "10") (pinfunction "10_10") (pintype "bidirectional"))
    )
    (net (code "99") (name "XMIPIDSI_D0_N") (class "Default")
      (node (ref "J3") (pin "23") (pinfunction "23_23") (pintype "bidirectional"))
    )
    (net (code "100") (name "XMIPIDSI_D0_P") (class "Default")
      (node (ref "J3") (pin "24") (pinfunction "24_24") (pintype "bidirectional"))
    )
    (net (code "101") (name "XMIPIDSI_D1_N") (class "Default")
      (node (ref "J3") (pin "25") (pinfunction "25_25") (pintype "bidirectional"))
    )
    (net (code "102") (name "XMIPIDSI_D1_P") (class "Default")
      (node (ref "J3") (pin "26") (pinfunction "26_26") (pintype "bidirectional"))
    )
    (net (code "103") (name "XMIPIDSI_D2_N") (class "Default")
      (node (ref "J3") (pin "27") (pinfunction "27_27") (pintype "bidirectional"))
    )
    (net (code "104") (name "XMIPIDSI_D2_P") (class "Default")
      (node (ref "J3") (pin "28") (pinfunction "28_28") (pintype "bidirectional"))
    )
    (net (code "105") (name "XMIPIDSI_D3_N") (class "Default")
      (node (ref "J3") (pin "29") (pinfunction "29_29") (pintype "bidirectional"))
    )
    (net (code "106") (name "XMIPIDSI_D3_P") (class "Default")
      (node (ref "J3") (pin "30") (pinfunction "30_30") (pintype "bidirectional"))
    )
    (net (code "107") (name "XMIPIDSI_DCLK_N") (class "Default")
      (node (ref "J3") (pin "21") (pinfunction "21_21") (pintype "bidirectional"))
    )
    (net (code "108") (name "XMIPIDSI_DCLK_P") (class "Default")
      (node (ref "J3") (pin "22") (pinfunction "22_22") (pintype "bidirectional"))
    )
    (net (code "109") (name "XNRESET") (class "Default")
      (node (ref "J4") (pin "11") (pinfunction "11_11") (pintype "bidirectional"))
      (node (ref "R12") (pin "2") (pinfunction "2_2") (pintype "passive"))
    )
    (net (code "110") (name "XOTG_D_N") (class "Default")
      (node (ref "J2") (pin "D-") (pinfunction "D-_D-") (pintype "bidirectional"))
      (node (ref "J3") (pin "45") (pinfunction "45_45") (pintype "bidirectional"))
    )
    (net (code "111") (name "XOTG_D_P") (class "Default")
      (node (ref "J2") (pin "D+") (pinfunction "D+_D+") (pintype "bidirectional"))
      (node (ref "J3") (pin "46") (pinfunction "46_46") (pintype "bidirectional"))
    )
    (net (code "112") (name "XOTG_ID") (class "Default")
      (node (ref "J2") (pin "ID") (pinfunction "ID_ID") (pintype "bidirectional"))
      (node (ref "J3") (pin "50") (pinfunction "50_50") (pintype "bidirectional"))
      (node (ref "R14") (pin "1") (pinfunction "1_1") (pintype "passive"))
    )
    (net (code "113") (name "XPGC27") (class "Default")
      (node (ref "J4") (pin "62") (pinfunction "62_62") (pintype "bidirectional"))
    )
    (net (code "114") (name "XPWERKEY") (class "Default")
      (node (ref "J4") (pin "9") (pinfunction "9_9") (pintype "bidirectional"))
      (node (ref "R9") (pin "2") (pinfunction "2_2") (pintype "passive"))
    )
    (net (code "115") (name "XPWM0") (class "Default")
      (node (ref "J4") (pin "26") (pinfunction "26_26") (pintype "bidirectional"))
      (node (ref "SV1") (pin "18") (pinfunction "18_18") (pintype "passive"))
    )
    (net (code "116") (name "XPWM1") (class "Default")
      (node (ref "J4") (pin "25") (pinfunction "25_25") (pintype "bidirectional"))
      (node (ref "SV1") (pin "17") (pinfunction "17_17") (pintype "passive"))
    )
    (net (code "117") (name "XSD0_CDN") (class "Default")
      (node (ref "J4") (pin "66") (pinfunction "66_66") (pintype "bidirectional"))
      (node (ref "J8") (pin "9") (pinfunction "DET_9") (pintype "bidirectional"))
      (node (ref "R17") (pin "1") (pinfunction "1_1") (pintype "passive"))
    )
    (net (code "118") (name "XSD0_CLK") (class "Default")
      (node (ref "J4") (pin "49") (pinfunction "49_49") (pintype "bidirectional"))
      (node (ref "J8") (pin "5") (pinfunction "CLK_5") (pintype "bidirectional"))
    )
    (net (code "119") (name "XSD0_CMD") (class "Default")
      (node (ref "J4") (pin "47") (pinfunction "47_47") (pintype "bidirectional"))
      (node (ref "J8") (pin "3") (pinfunction "CMD_3") (pintype "bidirectional"))
      (node (ref "R19") (pin "1") (pinfunction "1_1") (pintype "passive"))
    )
    (net (code "120") (name "XSD0_D0") (class "Default")
      (node (ref "J4") (pin "52") (pinfunction "52_52") (pintype "bidirectional"))
      (node (ref "J8") (pin "7") (pinfunction "DAT0_7") (pintype "bidirectional"))
      (node (ref "R20") (pin "1") (pinfunction "1_1") (pintype "passive"))
    )
    (net (code "121") (name "XSD0_D1") (class "Default")
      (node (ref "J4") (pin "51") (pinfunction "51_51") (pintype "bidirectional"))
      (node (ref "J8") (pin "8") (pinfunction "DAT1_8") (pintype "bidirectional"))
      (node (ref "R18") (pin "1") (pinfunction "1_1") (pintype "passive"))
    )
    (net (code "122") (name "XSD0_D2") (class "Default")
      (node (ref "J4") (pin "50") (pinfunction "50_50") (pintype "bidirectional"))
      (node (ref "J8") (pin "1") (pinfunction "DAT2_1") (pintype "bidirectional"))
      (node (ref "R21") (pin "1") (pinfunction "1_1") (pintype "passive"))
    )
    (net (code "123") (name "XSD0_D3") (class "Default")
      (node (ref "J4") (pin "48") (pinfunction "48_48") (pintype "bidirectional"))
      (node (ref "J8") (pin "2") (pinfunction "CD/DAT3_2") (pintype "bidirectional"))
      (node (ref "R22") (pin "1") (pinfunction "1_1") (pintype "passive"))
    )
    (net (code "124") (name "XSPI_CLK") (class "Default")
      (node (ref "J4") (pin "23") (pinfunction "23_23") (pintype "bidirectional"))
      (node (ref "SV1") (pin "15") (pinfunction "15_15") (pintype "passive"))
    )
    (net (code "125") (name "XSPI_CS") (class "Default")
      (node (ref "J4") (pin "24") (pinfunction "24_24") (pintype "bidirectional"))
      (node (ref "SV1") (pin "16") (pinfunction "16_16") (pintype "passive"))
    )
    (net (code "126") (name "XSPI_MISO") (class "Default")
      (node (ref "J4") (pin "21") (pinfunction "21_21") (pintype "bidirectional"))
      (node (ref "SV1") (pin "13") (pinfunction "13_13") (pintype "passive"))
    )
    (net (code "127") (name "XSPI_MOSI") (class "Default")
      (node (ref "J4") (pin "22") (pinfunction "22_22") (pintype "bidirectional"))
      (node (ref "SV1") (pin "14") (pinfunction "14_14") (pintype "passive"))
    )
    (net (code "128") (name "XUART_RX0") (class "Default")
      (node (ref "J4") (pin "46") (pinfunction "46_46") (pintype "bidirectional"))
      (node (ref "SV1") (pin "32") (pinfunction "32_32") (pintype "passive"))
    )
    (net (code "129") (name "XUART_RX1") (class "Default")
      (node (ref "J4") (pin "44") (pinfunction "44_44") (pintype "bidirectional"))
      (node (ref "SV1") (pin "30") (pinfunction "30_30") (pintype "passive"))
    )
    (net (code "130") (name "XUART_TX0") (class "Default")
      (node (ref "J4") (pin "45") (pinfunction "45_45") (pintype "bidirectional"))
      (node (ref "SV1") (pin "31") (pinfunction "31_31") (pintype "passive"))
    )
    (net (code "131") (name "XUART_TX1") (class "Default")
      (node (ref "J4") (pin "43") (pinfunction "43_43") (pintype "bidirectional"))
      (node (ref "SV1") (pin "29") (pinfunction "29_29") (pintype "passive"))
    )
    (net (code "132") (name "XUSBH_D_N") (class "Default")
      (node (ref "J3") (pin "47") (pinfunction "47_47") (pintype "bidirectional"))
      (node (ref "J5") (pin "2") (pinfunction "D-_2") (pintype "bidirectional"))
    )
    (net (code "133") (name "XUSBH_D_P") (class "Default")
      (node (ref "J3") (pin "48") (pinfunction "48_48") (pintype "bidirectional"))
      (node (ref "J5") (pin "3") (pinfunction "D+_3") (pintype "bidirectional"))
    )
    (net (code "134") (name "XVDDPWRON") (class "Default")
      (node (ref "J4") (pin "38") (pinfunction "38_38") (pintype "bidirectional"))
      (node (ref "R15") (pin "2") (pinfunction "2_2") (pintype "passive"))
    )
    (net (code "135") (name "unconnected-(IC2-~{OC}-Pad3)") (class "Default")
      (node (ref "IC2") (pin "3") (pinfunction "~{OC}_3") (pintype "bidirectional"))
    )
    (net (code "136") (name "unconnected-(IC4-~{OC}-Pad3)") (class "Default")
      (node (ref "IC4") (pin "3") (pinfunction "~{OC}_3") (pintype "bidirectional"))
    )
    (net (code "137") (name "unconnected-(J3-Pad49)") (class "Default")
      (node (ref "J3") (pin "49") (pinfunction "49_49") (pintype "bidirectional"))
    )
    (net (code "138") (name "unconnected-(J3-Pad51)") (class "Default")
      (node (ref "J3") (pin "51") (pinfunction "51_51") (pintype "bidirectional"))
    )
    (net (code "139") (name "unconnected-(J3-Pad53)") (class "Default")
      (node (ref "J3") (pin "53") (pinfunction "53_53") (pintype "bidirectional"))
    )
    (net (code "140") (name "unconnected-(J3-Pad57)") (class "Default")
      (node (ref "J3") (pin "57") (pinfunction "57_57") (pintype "bidirectional"))
    )
    (net (code "141") (name "unconnected-(J3-Pad58)") (class "Default")
      (node (ref "J3") (pin "58") (pinfunction "58_58") (pintype "bidirectional"))
    )
    (net (code "142") (name "unconnected-(J3-Pad61)") (class "Default")
      (node (ref "J3") (pin "61") (pinfunction "61_61") (pintype "bidirectional"))
    )
    (net (code "143") (name "unconnected-(J3-Pad62)") (class "Default")
      (node (ref "J3") (pin "62") (pinfunction "62_62") (pintype "bidirectional"))
    )
    (net (code "144") (name "unconnected-(J4-Pad7)") (class "Default")
      (node (ref "J4") (pin "7") (pinfunction "7_7") (pintype "bidirectional"))
    )
    (net (code "145") (name "unconnected-(J4-Pad53)") (class "Default")
      (node (ref "J4") (pin "53") (pinfunction "53_53") (pintype "bidirectional"))
    )
    (net (code "146") (name "unconnected-(J4-Pad69)") (class "Default")
      (node (ref "J4") (pin "69") (pinfunction "69_69") (pintype "bidirectional"))
    )
    (net (code "147") (name "unconnected-(J6-1-PadDTR)") (class "Default")
      (node (ref "J6") (pin "DTR") (pinfunction "1_DTR") (pintype "passive"))
    )
    (net (code "148") (name "unconnected-(J6-4-PadVCC)") (class "Default")
      (node (ref "J6") (pin "VCC") (pinfunction "4_VCC") (pintype "passive"))
    )
    (net (code "149") (name "unconnected-(J6-5-PadCTS)") (class "Default")
      (node (ref "J6") (pin "CTS") (pinfunction "5_CTS") (pintype "passive"))
    )
    (net (code "150") (name "unconnected-(J7-UTILITY-Pad14)") (class "Default")
      (node (ref "J7") (pin "14") (pinfunction "UTILITY_14") (pintype "bidirectional"))
    )
    (net (code "151") (name "unconnected-(S3-Pad3)") (class "Default")
      (node (ref "S3") (pin "3") (pinfunction "3_3") (pintype "bidirectional"))
    )
    (net (code "152") (name "unconnected-(S3-Pad6)") (class "Default")
      (node (ref "S3") (pin "6") (pinfunction "6_6") (pintype "bidirectional"))
    )
  )
)
